# 19.net
KiCad netlist of a schematic drawn in Altium Designer
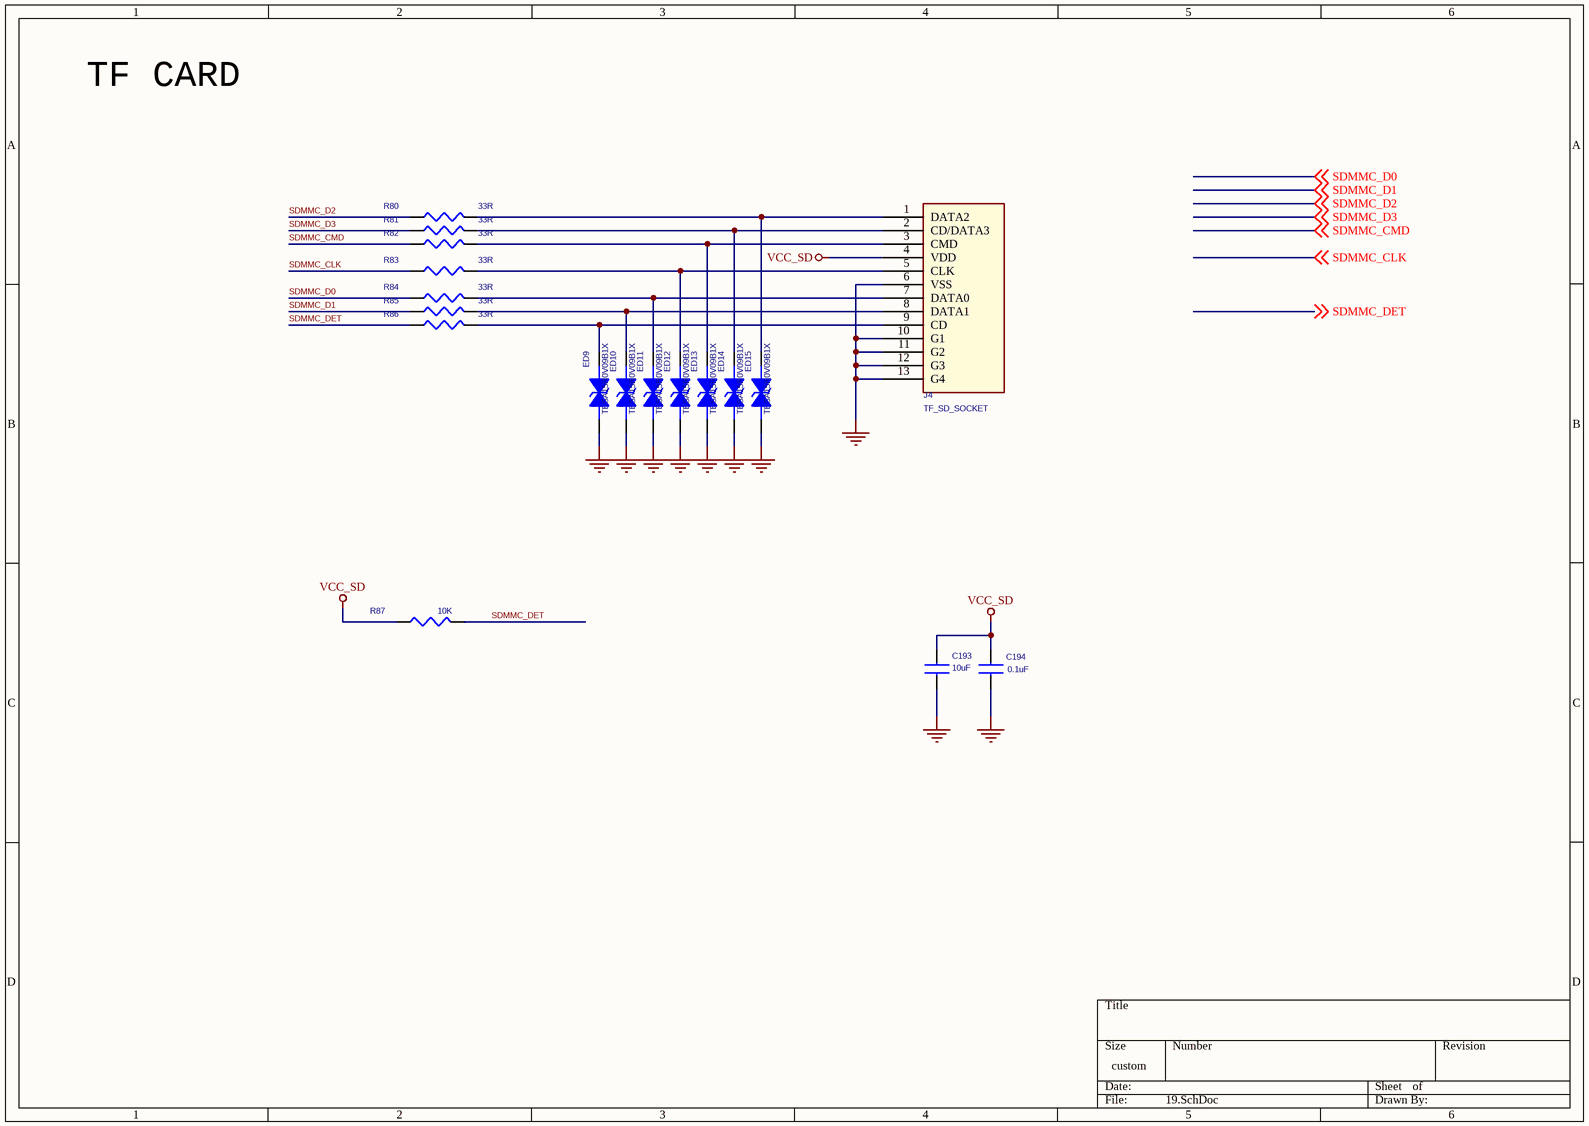
[diagram p0: 19.SchDoc]

(export (version "E")
  (design (tool "Eeschema 10.0.6"))
  (components
    (comp (ref "C193")
      (value "10uF")
      (footprint "C0603")
      (description "CAP,MLCC,10uF,+/-10%,X5R,6.3V,SMD0805")
      (libsource (lib "*") (part "CAP NP_Dup3"))
    )
    (comp (ref "C194")
      (value "0.1uF")
      (footprint "C0603")
      (description "CAP,MLCC,100nF,+/-10%,X7R,6.3V,SMD0402")
      (libsource (lib "*") (part "CAP NP_Dup3"))
    )
    (comp (ref "ED9")
      (value "TESA15R0V09B1X")
      (footprint "E0402N")
      (description "ESD Component,5V,30P,SMD,0402")
      (libsource (lib "*") (part "TVS"))
    )
    (comp (ref "ED10")
      (value "TESA15R0V09B1X")
      (footprint "E0402N")
      (description "ESD Component,5V,30P,SMD,0402")
      (libsource (lib "*") (part "TVS"))
    )
    (comp (ref "ED11")
      (value "TESA15R0V09B1X")
      (footprint "E0402N")
      (description "ESD Component,5V,30P,SMD,0402")
      (libsource (lib "*") (part "TVS"))
    )
    (comp (ref "ED12")
      (value "TESA15R0V09B1X")
      (footprint "E0402N")
      (description "ESD Component,5V,30P,SMD,0402")
      (libsource (lib "*") (part "TVS"))
    )
    (comp (ref "ED13")
      (value "TESA15R0V09B1X")
      (footprint "E0402N")
      (description "ESD Component,5V,30P,SMD,0402")
      (libsource (lib "*") (part "TVS"))
    )
    (comp (ref "ED14")
      (value "TESA15R0V09B1X")
      (footprint "E0402N")
      (description "ESD Component,5V,30P,SMD,0402")
      (libsource (lib "*") (part "TVS"))
    )
    (comp (ref "ED15")
      (value "TESA15R0V09B1X")
      (footprint "E0402N")
      (description "ESD Component,5V,30P,SMD,0402")
      (libsource (lib "*") (part "TVS"))
    )
    (comp (ref "J4")
      (value "TF_SD_SOCKET")
      (footprint "TF-CARDKLJ07002")
      (libsource (lib "*") (part "SD_SOCKET_0"))
    )
    (comp (ref "R80") (value "33R") (footprint "r0402") (libsource (lib "*") (part "RESISTOR_1_Dup2")))
    (comp (ref "R81") (value "33R") (footprint "r0402") (libsource (lib "*") (part "RESISTOR_1_Dup2")))
    (comp (ref "R82") (value "33R") (footprint "r0402") (libsource (lib "*") (part "RESISTOR_1_Dup2")))
    (comp (ref "R83") (value "33R") (footprint "r0402") (libsource (lib "*") (part "RESISTOR_1_Dup2")))
    (comp (ref "R84") (value "33R") (footprint "r0402") (libsource (lib "*") (part "RESISTOR_1_Dup2")))
    (comp (ref "R85") (value "33R") (footprint "r0402") (libsource (lib "*") (part "RESISTOR_1_Dup2")))
    (comp (ref "R86") (value "33R") (footprint "r0402") (libsource (lib "*") (part "RESISTOR_1_Dup2")))
    (comp (ref "R87") (value "10K") (footprint "r0402") (libsource (lib "*") (part "RESISTOR_1_Dup2")))
  )
  (nets
    (net (code "1") (name "GND") (class "Default")
      (node (ref "C193") (pin "1") (pinfunction "1_1") (pintype "passive"))
      (node (ref "C194") (pin "2") (pinfunction "2_2") (pintype "passive"))
      (node (ref "ED10") (pin "2") (pinfunction "2_2") (pintype "passive"))
      (node (ref "ED11") (pin "2") (pinfunction "2_2") (pintype "passive"))
      (node (ref "ED12") (pin "2") (pinfunction "2_2") (pintype "passive"))
      (node (ref "ED13") (pin "2") (pinfunction "2_2") (pintype "passive"))
      (node (ref "ED14") (pin "2") (pinfunction "2_2") (pintype "passive"))
      (node (ref "ED15") (pin "2") (pinfunction "2_2") (pintype "passive"))
      (node (ref "ED9") (pin "2") (pinfunction "2_2") (pintype "passive"))
      (node (ref "J4") (pin "10") (pinfunction "G1_10") (pintype "passive"))
      (node (ref "J4") (pin "11") (pinfunction "G2_11") (pintype "passive"))
      (node (ref "J4") (pin "12") (pinfunction "G3_12") (pintype "passive"))
      (node (ref "J4") (pin "13") (pinfunction "G4_13") (pintype "passive"))
      (node (ref "J4") (pin "6") (pinfunction "VSS_6") (pintype "passive"))
    )
    (net (code "2") (name "Net-(J4-CD)") (class "Default")
      (node (ref "ED9") (pin "1") (pinfunction "1_1") (pintype "passive"))
      (node (ref "J4") (pin "9") (pinfunction "CD_9") (pintype "passive"))
      (node (ref "R86") (pin "2") (pinfunction "2_2") (pintype "passive"))
    )
    (net (code "3") (name "Net-(J4-CD{slash}DATA3)") (class "Default")
      (node (ref "ED14") (pin "1") (pinfunction "1_1") (pintype "passive"))
      (node (ref "J4") (pin "2") (pinfunction "CD/DATA3_2") (pintype "passive"))
      (node (ref "R81") (pin "2") (pinfunction "2_2") (pintype "passive"))
    )
    (net (code "4") (name "Net-(J4-CLK)") (class "Default")
      (node (ref "ED12") (pin "1") (pinfunction "1_1") (pintype "passive"))
      (node (ref "J4") (pin "5") (pinfunction "CLK_5") (pintype "passive"))
      (node (ref "R83") (pin "2") (pinfunction "2_2") (pintype "passive"))
    )
    (net (code "5") (name "Net-(J4-CMD)") (class "Default")
      (node (ref "ED13") (pin "1") (pinfunction "1_1") (pintype "passive"))
      (node (ref "J4") (pin "3") (pinfunction "CMD_3") (pintype "passive"))
      (node (ref "R82") (pin "2") (pinfunction "2_2") (pintype "passive"))
    )
    (net (code "6") (name "Net-(J4-DATA0)") (class "Default")
      (node (ref "ED11") (pin "1") (pinfunction "1_1") (pintype "passive"))
      (node (ref "J4") (pin "7") (pinfunction "DATA0_7") (pintype "passive"))
      (node (ref "R84") (pin "2") (pinfunction "2_2") (pintype "passive"))
    )
    (net (code "7") (name "Net-(J4-DATA1)") (class "Default")
      (node (ref "ED10") (pin "1") (pinfunction "1_1") (pintype "passive"))
      (node (ref "J4") (pin "8") (pinfunction "DATA1_8") (pintype "passive"))
      (node (ref "R85") (pin "2") (pinfunction "2_2") (pintype "passive"))
    )
    (net (code "8") (name "Net-(J4-DATA2)") (class "Default")
      (node (ref "ED15") (pin "1") (pinfunction "1_1") (pintype "passive"))
      (node (ref "J4") (pin "1") (pinfunction "DATA2_1") (pintype "passive"))
      (node (ref "R80") (pin "2") (pinfunction "2_2") (pintype "passive"))
    )
    (net (code "9") (name "SDMMC_CLK") (class "Default")
      (node (ref "R83") (pin "1") (pinfunction "1_1") (pintype "passive"))
    )
    (net (code "10") (name "SDMMC_CMD") (class "Default")
      (node (ref "R82") (pin "1") (pinfunction "1_1") (pintype "passive"))
    )
    (net (code "11") (name "SDMMC_D0") (class "Default")
      (node (ref "R84") (pin "1") (pinfunction "1_1") (pintype "passive"))
    )
    (net (code "12") (name "SDMMC_D1") (class "Default")
      (node (ref "R85") (pin "1") (pinfunction "1_1") (pintype "passive"))
    )
    (net (code "13") (name "SDMMC_D2") (class "Default")
      (node (ref "R80") (pin "1") (pinfunction "1_1") (pintype "passive"))
    )
    (net (code "14") (name "SDMMC_D3") (class "Default")
      (node (ref "R81") (pin "1") (pinfunction "1_1") (pintype "passive"))
    )
    (net (code "15") (name "SDMMC_DET") (class "Default")
      (node (ref "R86") (pin "1") (pinfunction "1_1") (pintype "passive"))
      (node (ref "R87") (pin "2") (pinfunction "2_2") (pintype "passive"))
    )
    (net (code "16") (name "VCC_SD") (class "Default")
      (node (ref "C193") (pin "2") (pinfunction "2_2") (pintype "passive"))
      (node (ref "C194") (pin "1") (pinfunction "1_1") (pintype "passive"))
      (node (ref "J4") (pin "4") (pinfunction "VDD_4") (pintype "passive"))
      (node (ref "R87") (pin "1") (pinfunction "1_1") (pintype "passive"))
    )
  )
)
